# schematic.net
KiCad netlist of a schematic drawn in EAGLE
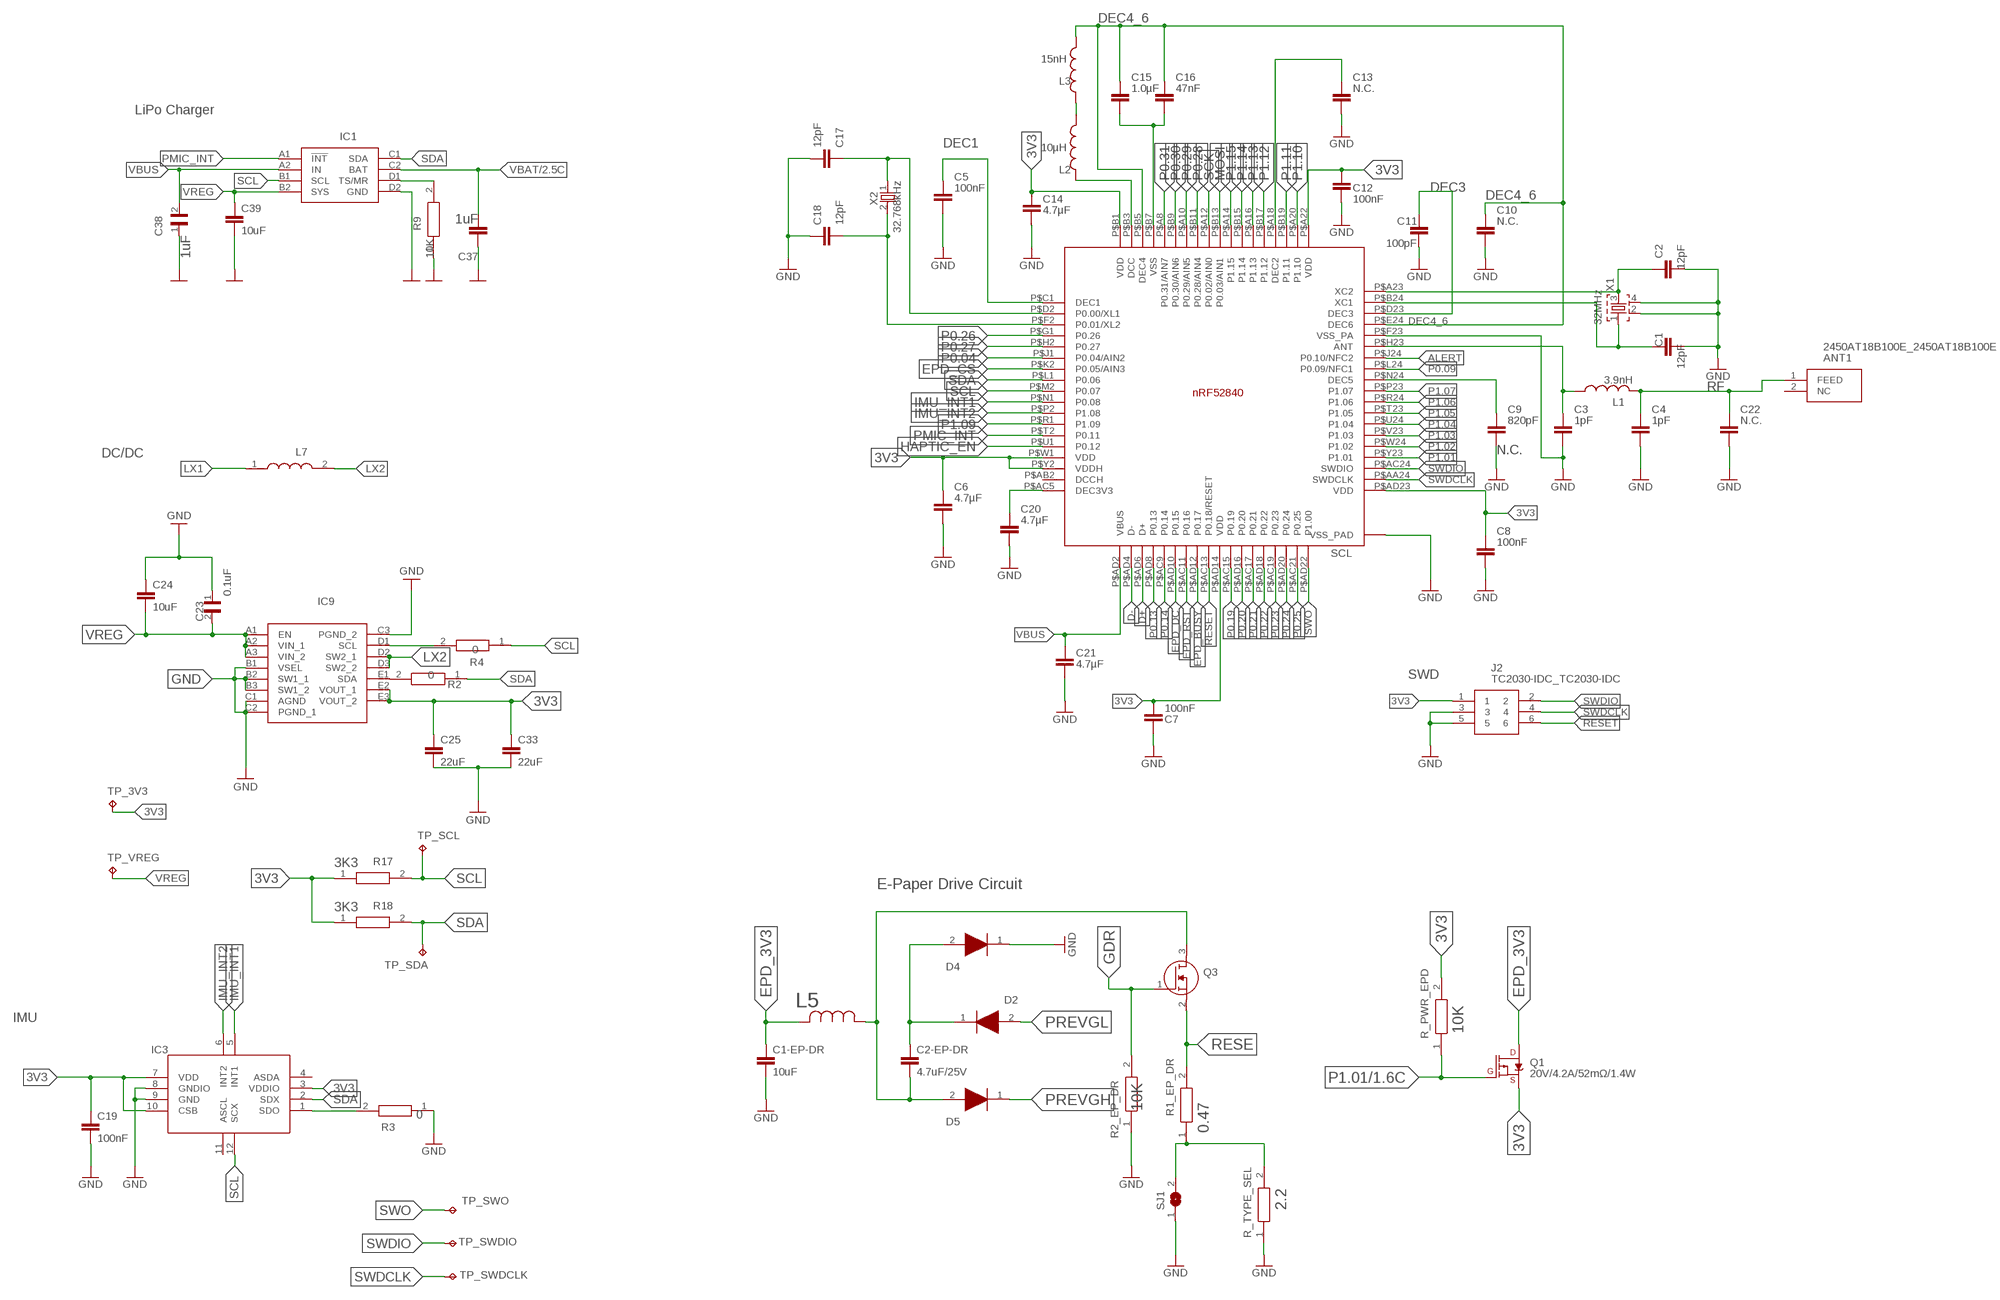
[diagram p0: schematic, sheet 1, part 1 of 2]
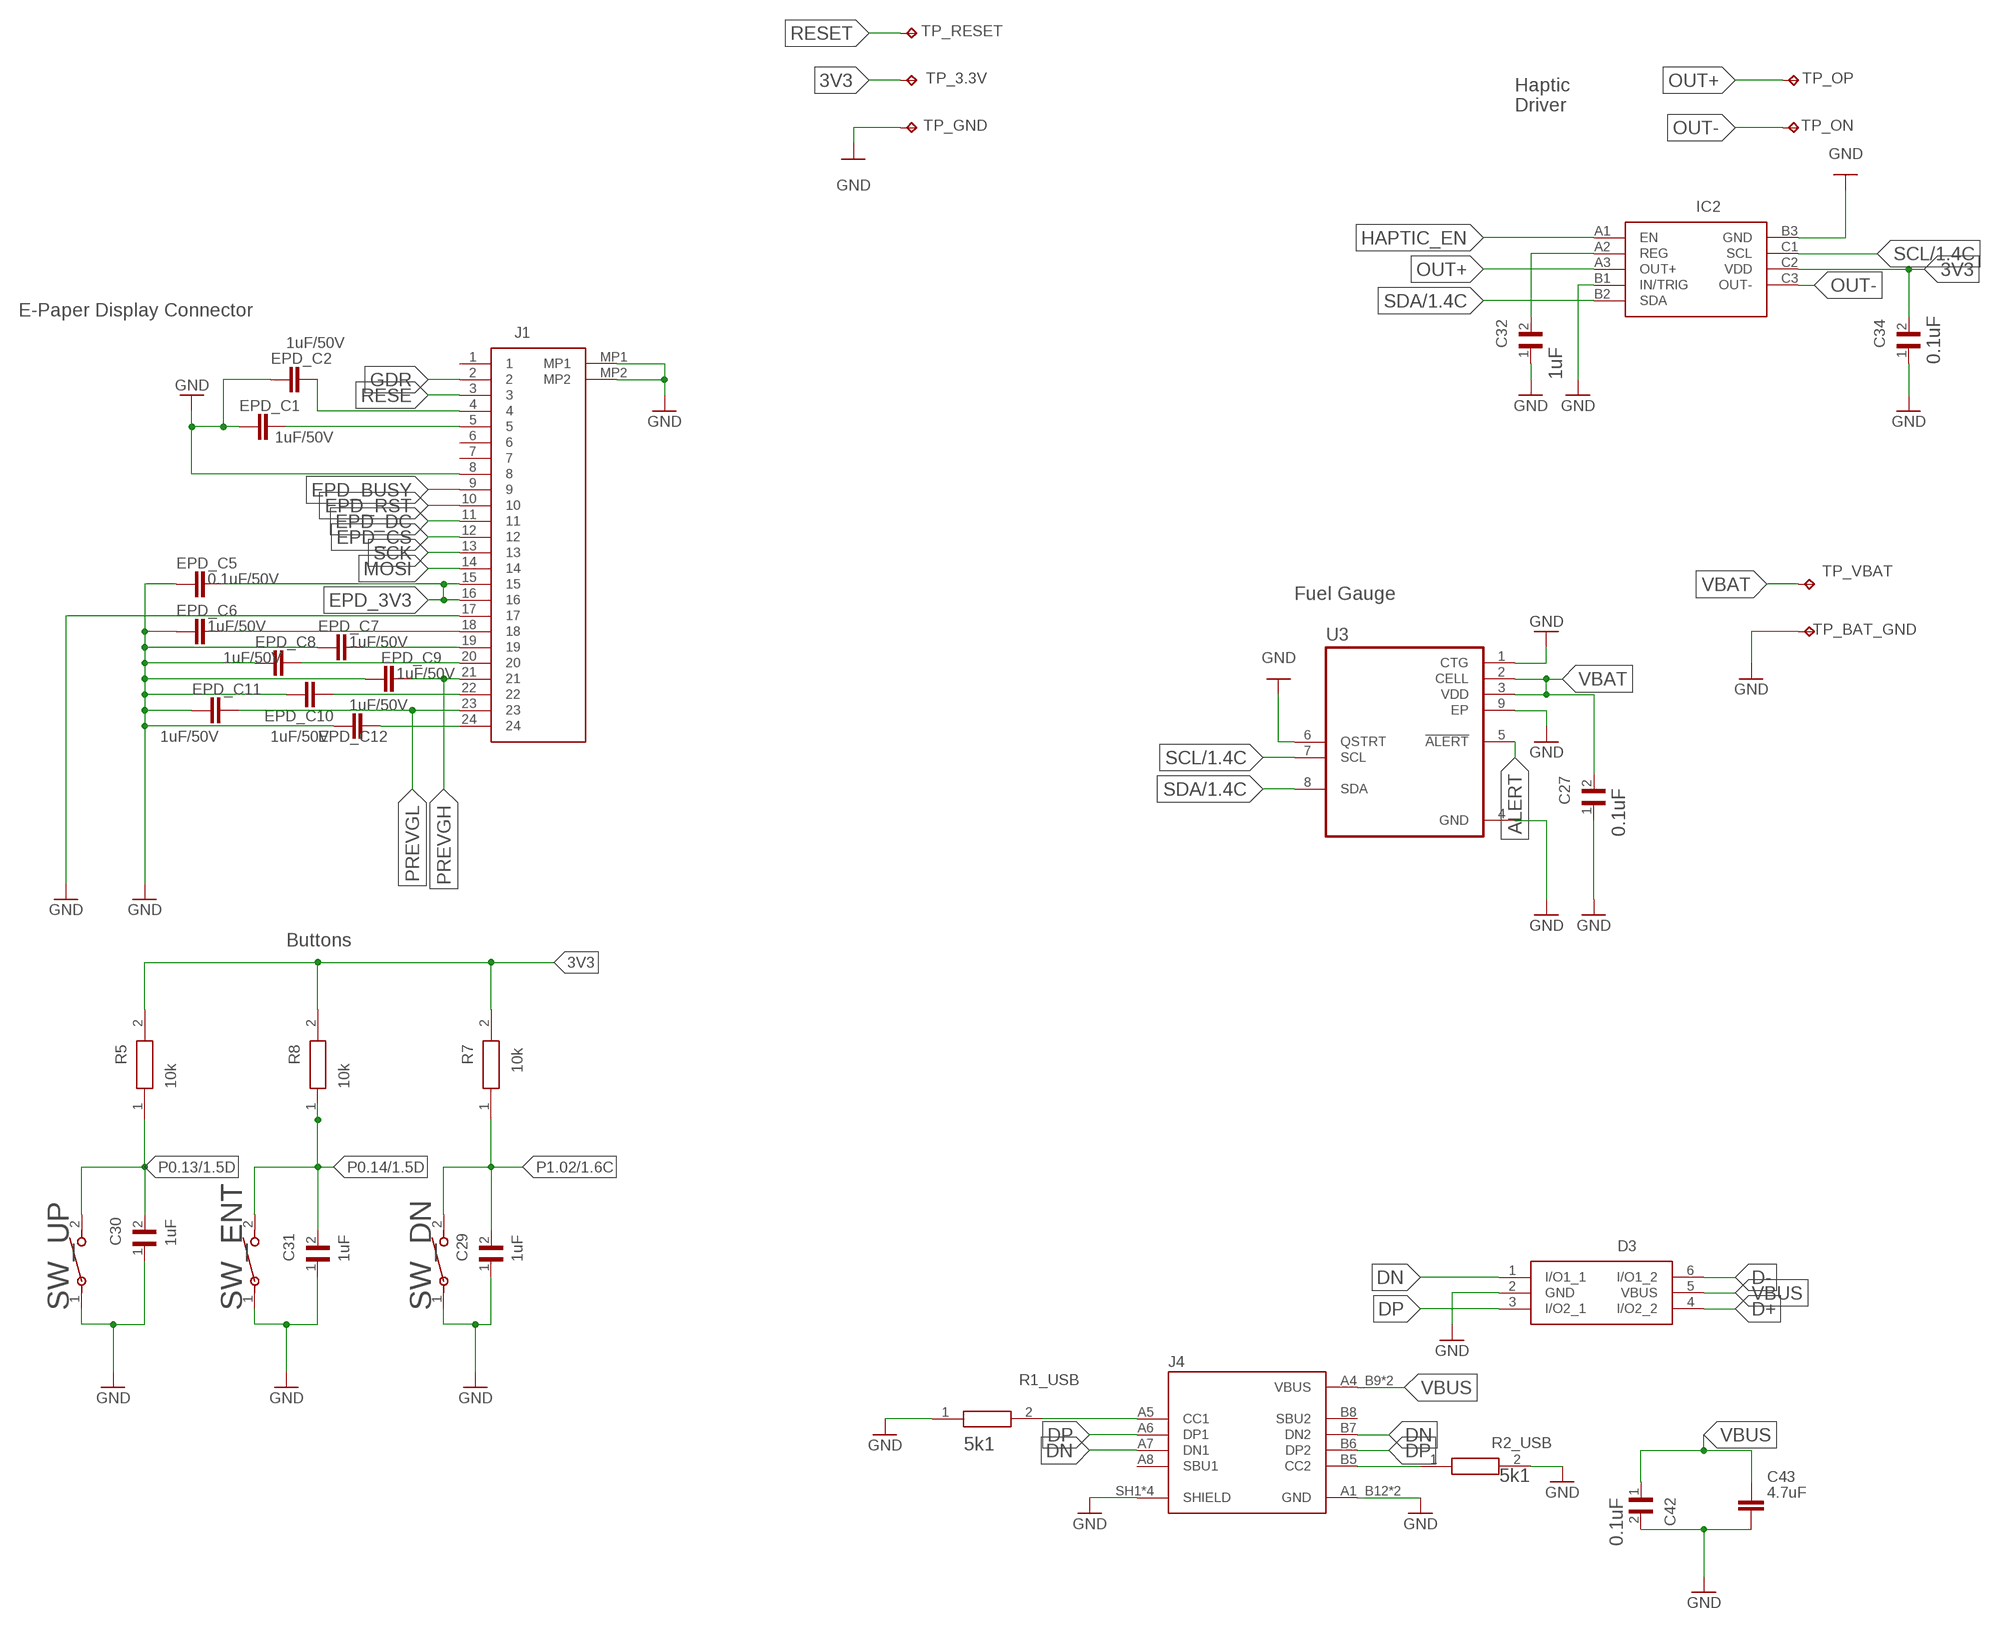
[diagram p1: schematic, sheet 1, part 2 of 2]

(export (version "E")
  (design (tool "Eeschema 10.0.6"))
  (components
    (comp (ref "ANT1")
      (value "2450AT18B100E_2450AT18B100E")
      (footprint "eagle-import:2450AT18B100E_ANTC3216X140N")
      (fields
        (field (name "ARROW_PART_NUMBER") "2450AT18B100E")
        (field (name "MOUSER_PART_NUMBER") "609-2450AT18B100E")
      )
      (libsource (lib "eagle-import") (part "2450AT18B100E_2450AT18B100E"))
    )
    (comp (ref "C1")
      (value "12pF")
      (footprint "eagle-import:NORDIC_NRF_3_RESC0201_L")
      (libsource (lib "eagle-import") (part "NORDIC_NRF_3_CAPACITOR_0201_L"))
    )
    (comp (ref "C1-EP-DR")
      (value "10uF")
      (footprint "eagle-import:NORDIC_NRF_3_RESC0402_L")
      (libsource (lib "eagle-import") (part "NORDIC_NRF_3_CAPACITOR_0402_L"))
    )
    (comp (ref "C2")
      (value "12pF")
      (footprint "eagle-import:NORDIC_NRF_3_RESC0201_L")
      (libsource (lib "eagle-import") (part "NORDIC_NRF_3_CAPACITOR_0201_L"))
    )
    (comp (ref "C2-EP-DR")
      (value "4.7uF/25V")
      (footprint "eagle-import:NORDIC_NRF_3_RESC0402_L")
      (libsource (lib "eagle-import") (part "NORDIC_NRF_3_CAPACITOR_0402_L"))
    )
    (comp (ref "C3")
      (value "1pF")
      (footprint "eagle-import:NORDIC_NRF_3_RESC0201_L")
      (libsource (lib "eagle-import") (part "NORDIC_NRF_3_CAPACITOR_0201_L"))
    )
    (comp (ref "C4")
      (value "1pF")
      (footprint "eagle-import:NORDIC_NRF_3_RESC0201_L")
      (libsource (lib "eagle-import") (part "NORDIC_NRF_3_CAPACITOR_0201_L"))
    )
    (comp (ref "C5")
      (value "100nF")
      (footprint "eagle-import:NORDIC_NRF_3_RESC0201_L")
      (libsource (lib "eagle-import") (part "NORDIC_NRF_3_CAPACITOR_0201_L"))
    )
    (comp (ref "C6")
      (value "4.7µF")
      (footprint "eagle-import:NORDIC_NRF_3_RESC0402_L")
      (libsource (lib "eagle-import") (part "NORDIC_NRF_3_CAPACITOR_0402_L"))
    )
    (comp (ref "C7")
      (value "100nF")
      (footprint "eagle-import:NORDIC_NRF_3_RESC0201_L")
      (libsource (lib "eagle-import") (part "NORDIC_NRF_3_CAPACITOR_0201_L"))
    )
    (comp (ref "C8")
      (value "100nF")
      (footprint "eagle-import:NORDIC_NRF_3_RESC0201_L")
      (libsource (lib "eagle-import") (part "NORDIC_NRF_3_CAPACITOR_0201_L"))
    )
    (comp (ref "C9")
      (value "820pF")
      (footprint "eagle-import:NORDIC_NRF_3_RESC0201_L")
      (libsource (lib "eagle-import") (part "NORDIC_NRF_3_CAPACITOR_0201_L"))
    )
    (comp (ref "C10")
      (value "N.C.")
      (footprint "eagle-import:NORDIC_NRF_3_RESC0201_L")
      (libsource (lib "eagle-import") (part "NORDIC_NRF_3_CAPACITOR_0201_L"))
    )
    (comp (ref "C11")
      (value "100pF")
      (footprint "eagle-import:NORDIC_NRF_3_RESC0201_L")
      (libsource (lib "eagle-import") (part "NORDIC_NRF_3_CAPACITOR_0201_L"))
    )
    (comp (ref "C12")
      (value "100nF")
      (footprint "eagle-import:NORDIC_NRF_3_RESC0201_L")
      (libsource (lib "eagle-import") (part "NORDIC_NRF_3_CAPACITOR_0201_L"))
    )
    (comp (ref "C13")
      (value "N.C.")
      (footprint "eagle-import:NORDIC_NRF_3_RESC0201_L")
      (libsource (lib "eagle-import") (part "NORDIC_NRF_3_CAPACITOR_0201_L"))
    )
    (comp (ref "C14")
      (value "4.7µF")
      (footprint "eagle-import:NORDIC_NRF_3_RESC0402_L")
      (libsource (lib "eagle-import") (part "NORDIC_NRF_3_CAPACITOR_0402_L"))
    )
    (comp (ref "C15")
      (value "1.0µF")
      (footprint "eagle-import:NORDIC_NRF_3_RESC0402_L")
      (libsource (lib "eagle-import") (part "NORDIC_NRF_3_CAPACITOR_0402_L"))
    )
    (comp (ref "C16")
      (value "47nF")
      (footprint "eagle-import:NORDIC_NRF_3_RESC0201_L")
      (libsource (lib "eagle-import") (part "NORDIC_NRF_3_CAPACITOR_0201_L"))
    )
    (comp (ref "C17")
      (value "12pF")
      (footprint "eagle-import:NORDIC_NRF_3_RESC0201_L")
      (libsource (lib "eagle-import") (part "NORDIC_NRF_3_CAPACITOR_0201_L"))
    )
    (comp (ref "C18")
      (value "12pF")
      (footprint "eagle-import:NORDIC_NRF_3_RESC0201_L")
      (libsource (lib "eagle-import") (part "NORDIC_NRF_3_CAPACITOR_0201_L"))
    )
    (comp (ref "C19")
      (value "100nF")
      (footprint "eagle-import:NORDIC_NRF_3_RESC0201_L")
      (libsource (lib "eagle-import") (part "NORDIC_NRF_3_CAPACITOR_0201_L"))
    )
    (comp (ref "C20")
      (value "4.7µF")
      (footprint "eagle-import:NORDIC_NRF_3_RESC0402_L")
      (libsource (lib "eagle-import") (part "NORDIC_NRF_3_CAPACITOR_0402_L"))
    )
    (comp (ref "C21")
      (value "4.7µF")
      (footprint "eagle-import:NORDIC_NRF_3_RESC0402_L")
      (libsource (lib "eagle-import") (part "NORDIC_NRF_3_CAPACITOR_0402_L"))
    )
    (comp (ref "C22")
      (value "N.C.")
      (footprint "eagle-import:NORDIC_NRF_3_RESC0201_L")
      (libsource (lib "eagle-import") (part "NORDIC_NRF_3_CAPACITOR_0201_L"))
    )
    (comp (ref "C23")
      (value "GRM011R60J152KE01L_2_GRM011R60J152KE01L")
      (footprint "eagle-import:GRM011R60J152KE01L_2_CAPC0201X13N")
      (fields
        (field (name "MF") "Murata")
        (field (name "MP") "GRM011R60J152KE01L")
        (field (name "C23") "0.1uF")
      )
      (libsource (lib "eagle-import") (part "GRM011R60J152KE01L_2_GRM011R60J152KE01L"))
    )
    (comp (ref "C24")
      (value "10uF")
      (footprint "eagle-import:NORDIC_NRF_3_RESC0402_L")
      (libsource (lib "eagle-import") (part "NORDIC_NRF_3_CAPACITOR_0402_L"))
    )
    (comp (ref "C25")
      (value "22uF")
      (footprint "eagle-import:NORDIC_NRF_3_RESC0402_L")
      (libsource (lib "eagle-import") (part "NORDIC_NRF_3_CAPACITOR_0402_L"))
    )
    (comp (ref "C27")
      (value "GRM011R60J152KE01L_2_GRM011R60J152KE01L")
      (footprint "eagle-import:GRM011R60J152KE01L_2_CAPC0201X13N")
      (fields
        (field (name "MF") "Murata")
        (field (name "MP") "GRM011R60J152KE01L")
        (field (name "C27") "0.1uF")
      )
      (libsource (lib "eagle-import") (part "GRM011R60J152KE01L_2_GRM011R60J152KE01L"))
    )
    (comp (ref "C29")
      (value "GRM011R60J152KE01L_2_GRM011R60J152KE01L")
      (footprint "eagle-import:GRM011R60J152KE01L_2_CAPC0201X13N")
      (fields
        (field (name "MF") "Murata")
        (field (name "MP") "GRM011R60J152KE01L")
        (field (name "C29") "1uF")
      )
      (libsource (lib "eagle-import") (part "GRM011R60J152KE01L_2_GRM011R60J152KE01L"))
    )
    (comp (ref "C30")
      (value "GRM011R60J152KE01L_2_GRM011R60J152KE01L")
      (footprint "eagle-import:GRM011R60J152KE01L_2_CAPC0201X13N")
      (fields
        (field (name "MF") "Murata")
        (field (name "MP") "GRM011R60J152KE01L")
        (field (name "C30") "1uF")
      )
      (libsource (lib "eagle-import") (part "GRM011R60J152KE01L_2_GRM011R60J152KE01L"))
    )
    (comp (ref "C31")
      (value "GRM011R60J152KE01L_2_GRM011R60J152KE01L")
      (footprint "eagle-import:GRM011R60J152KE01L_2_CAPC0201X13N")
      (fields
        (field (name "MF") "Murata")
        (field (name "MP") "GRM011R60J152KE01L")
        (field (name "C31") "1uF")
      )
      (libsource (lib "eagle-import") (part "GRM011R60J152KE01L_2_GRM011R60J152KE01L"))
    )
    (comp (ref "C32")
      (value "GRM011R60J152KE01L_2_GRM011R60J152KE01L")
      (footprint "eagle-import:GRM011R60J152KE01L_2_CAPC0201X13N")
      (fields
        (field (name "MF") "Murata")
        (field (name "MP") "GRM011R60J152KE01L")
        (field (name "C32") "1uF")
      )
      (libsource (lib "eagle-import") (part "GRM011R60J152KE01L_2_GRM011R60J152KE01L"))
    )
    (comp (ref "C33")
      (value "22uF")
      (footprint "eagle-import:NORDIC_NRF_3_RESC0402_L")
      (libsource (lib "eagle-import") (part "NORDIC_NRF_3_CAPACITOR_0402_L"))
    )
    (comp (ref "C34")
      (value "GRM011R60J152KE01L_2_GRM011R60J152KE01L")
      (footprint "eagle-import:GRM011R60J152KE01L_2_CAPC0201X13N")
      (fields
        (field (name "MF") "Murata")
        (field (name "MP") "GRM011R60J152KE01L")
        (field (name "C34") "0.1uF")
      )
      (libsource (lib "eagle-import") (part "GRM011R60J152KE01L_2_GRM011R60J152KE01L"))
    )
    (comp (ref "C37")
      (value "NORDIC_NRF_3_CAPACITOR_0402_L")
      (footprint "eagle-import:NORDIC_NRF_3_RESC0402_L")
      (fields (field (name "GF") "1uF"))
      (libsource (lib "eagle-import") (part "NORDIC_NRF_3_CAPACITOR_0402_L"))
    )
    (comp (ref "C38")
      (value "GRM011R60J152KE01L_2_GRM011R60J152KE01L")
      (footprint "eagle-import:GRM011R60J152KE01L_2_CAPC0201X13N")
      (fields (field (name "MF") "Murata") (field (name "MP") "GRM011R60J152KE01L") (field (name "D") "1uF"))
      (libsource (lib "eagle-import") (part "GRM011R60J152KE01L_2_GRM011R60J152KE01L"))
    )
    (comp (ref "C39")
      (value "10uF")
      (footprint "eagle-import:NORDIC_NRF_3_RESC0402_L")
      (libsource (lib "eagle-import") (part "NORDIC_NRF_3_CAPACITOR_0402_L"))
    )
    (comp (ref "C42")
      (value "GRM011R60J152KE01L_2_GRM011R60J152KE01L")
      (footprint "eagle-import:GRM011R60J152KE01L_2_CAPC0201X13N")
      (fields
        (field (name "MF") "Murata")
        (field (name "MP") "GRM011R60J152KE01L")
        (field (name "C42") "0.1uF")
      )
      (libsource (lib "eagle-import") (part "GRM011R60J152KE01L_2_GRM011R60J152KE01L"))
    )
    (comp (ref "C43")
      (value "4.7uF")
      (footprint "eagle-import:NORDIC_NRF_3_RESC0402_L")
      (libsource (lib "eagle-import") (part "NORDIC_NRF_3_CAPACITOR_0402_L"))
    )
    (comp (ref "D2")
      (value "ESP32_C6_LIBRARY_5_MBR0530")
      (footprint "eagle-import:ESP32_C6_LIBRARY_5_SOD3716X135N")
      (fields (field (name "MF") "ON Semiconductor") (field (name "MP") "MBR0530"))
      (libsource (lib "eagle-import") (part "ESP32_C6_LIBRARY_5_MBR0530"))
    )
    (comp (ref "D3")
      (value "ESP32_C6_LIBRARY_3_USBLC6-2SC6Y")
      (footprint "eagle-import:ESP32_C6_LIBRARY_3_SOT95P280X145-6N")
      (fields (field (name "MF") "STMicroelectronics") (field (name "MP") "USBLC6-2SC6Y"))
      (libsource (lib "eagle-import") (part "ESP32_C6_LIBRARY_3_USBLC6-2SC6Y"))
    )
    (comp (ref "D4")
      (value "ESP32_C6_LIBRARY_5_MBR0530")
      (footprint "eagle-import:ESP32_C6_LIBRARY_5_SOD3716X135N")
      (fields (field (name "MF") "ON Semiconductor") (field (name "MP") "MBR0530"))
      (libsource (lib "eagle-import") (part "ESP32_C6_LIBRARY_5_MBR0530"))
    )
    (comp (ref "D5")
      (value "ESP32_C6_LIBRARY_5_MBR0530")
      (footprint "eagle-import:ESP32_C6_LIBRARY_5_SOD3716X135N")
      (fields (field (name "MF") "ON Semiconductor") (field (name "MP") "MBR0530"))
      (libsource (lib "eagle-import") (part "ESP32_C6_LIBRARY_5_MBR0530"))
    )
    (comp (ref "EPD_C1")
      (value "1uF/50V")
      (footprint "eagle-import:NORDIC_NRF_3_RESC0402_L")
      (libsource (lib "eagle-import") (part "NORDIC_NRF_3_CAPACITOR_0402_L"))
    )
    (comp (ref "EPD_C2")
      (value "1uF/50V")
      (footprint "eagle-import:NORDIC_NRF_3_RESC0402_L")
      (libsource (lib "eagle-import") (part "NORDIC_NRF_3_CAPACITOR_0402_L"))
    )
    (comp (ref "EPD_C5")
      (value "0.1uF/50V")
      (footprint "eagle-import:NORDIC_NRF_3_RESC0402_L")
      (libsource (lib "eagle-import") (part "NORDIC_NRF_3_CAPACITOR_0402_L"))
    )
    (comp (ref "EPD_C6")
      (value "1uF/50V")
      (footprint "eagle-import:NORDIC_NRF_3_RESC0402_L")
      (libsource (lib "eagle-import") (part "NORDIC_NRF_3_CAPACITOR_0402_L"))
    )
    (comp (ref "EPD_C7")
      (value "1uF/50V")
      (footprint "eagle-import:NORDIC_NRF_3_RESC0402_L")
      (libsource (lib "eagle-import") (part "NORDIC_NRF_3_CAPACITOR_0402_L"))
    )
    (comp (ref "EPD_C8")
      (value "1uF/50V")
      (footprint "eagle-import:NORDIC_NRF_3_RESC0402_L")
      (libsource (lib "eagle-import") (part "NORDIC_NRF_3_CAPACITOR_0402_L"))
    )
    (comp (ref "EPD_C9")
      (value "1uF/50V")
      (footprint "eagle-import:NORDIC_NRF_3_RESC0402_L")
      (libsource (lib "eagle-import") (part "NORDIC_NRF_3_CAPACITOR_0402_L"))
    )
    (comp (ref "EPD_C10")
      (value "1uF/50V")
      (footprint "eagle-import:NORDIC_NRF_3_RESC0402_L")
      (libsource (lib "eagle-import") (part "NORDIC_NRF_3_CAPACITOR_0402_L"))
    )
    (comp (ref "EPD_C11")
      (value "1uF/50V")
      (footprint "eagle-import:NORDIC_NRF_3_RESC0402_L")
      (libsource (lib "eagle-import") (part "NORDIC_NRF_3_CAPACITOR_0402_L"))
    )
    (comp (ref "EPD_C12")
      (value "1uF/50V")
      (footprint "eagle-import:NORDIC_NRF_3_RESC0402_L")
      (libsource (lib "eagle-import") (part "NORDIC_NRF_3_CAPACITOR_0402_L"))
    )
    (comp (ref "IC1")
      (value "BQ25180YBGR_BQ25180YBGR")
      (footprint "eagle-import:BQ25180YBGR_BGA8C40P2X4_100X155X50")
      (fields
        (field (name "ARROW_PART_NUMBER") "BQ25180YBGR")
        (field (name "MOUSER_PART_NUMBER") "595-BQ25180YBGR")
      )
      (libsource (lib "eagle-import") (part "BQ25180YBGR_BQ25180YBGR"))
    )
    (comp (ref "IC2")
      (value "DRV2605YZFR_DRV2605YZFR")
      (footprint "eagle-import:DRV2605YZFR_BGA9C50P3X3_144X144X62")
      (fields (field (name "ARROW_PART_NUMBER") "DRV2605YZFR"))
      (libsource (lib "eagle-import") (part "DRV2605YZFR_DRV2605YZFR"))
    )
    (comp (ref "IC3")
      (value "BMA423_BMA423")
      (footprint "eagle-import:BMA423_BMA423")
      (fields (field (name "ARROW_PART_NUMBER") "BMA423") (field (name "MOUSER_PART_NUMBER") "262-BMA423"))
      (libsource (lib "eagle-import") (part "BMA423_BMA423"))
    )
    (comp (ref "IC9")
      (value "RT6160AWSC_RT6160AWSC")
      (footprint "eagle-import:RT6160AWSC_BGA15C40P3X5_140X230X60")
      (fields
        (field (name "MANUFACTURER_PART_NUMBER") "RT6160AWSC")
        (field (name "MOUSER_PART_NUMBER") "835-RT6160AWSC")
      )
      (libsource (lib "eagle-import") (part "RT6160AWSC_RT6160AWSC"))
    )
    (comp (ref "J1")
      (value "503480-2400_503480-2400")
      (footprint "eagle-import:503480-2400_5034802400")
      (fields
        (field (name "MANUFACTURER_PART_NUMBER") "503480-2400")
        (field (name "MOUSER_PART_NUMBER") "538-503480-2400")
      )
      (libsource (lib "eagle-import") (part "503480-2400_503480-2400"))
    )
    (comp (ref "J2")
      (value "TC2030-IDC_TC2030-IDC")
      (footprint "eagle-import:TC2030-IDC_TC2030IDC")
      (fields (field (name "MANUFACTURER_PART_NUMBER") "TC2030-IDC"))
      (libsource (lib "eagle-import") (part "TC2030-IDC_TC2030-IDC"))
    )
    (comp (ref "J4")
      (value "KH-TYPE-C-16P_KH-TYPE-C-16P")
      (footprint "eagle-import:KH-TYPE-C-16P_KINGHELM_KH-TYPE-C-16P")
      (fields (field (name "MF") "kinghelm") (field (name "MP") "KH-TYPE-C-16P"))
      (libsource (lib "eagle-import") (part "KH-TYPE-C-16P_KH-TYPE-C-16P"))
    )
    (comp (ref "L1")
      (value "3.9nH")
      (footprint "eagle-import:NORDIC_NRF_2_RESC0201_L")
      (libsource (lib "eagle-import") (part "NORDIC_NRF_2_INDUCTOR_0201_L"))
    )
    (comp (ref "L2")
      (value "10µH")
      (footprint "eagle-import:NORDIC_NRF_2_RESC0201_L")
      (libsource (lib "eagle-import") (part "NORDIC_NRF_2_INDUCTOR_0201_L"))
    )
    (comp (ref "L3")
      (value "15nH")
      (footprint "eagle-import:NORDIC_NRF_2_RESC0201_L")
      (libsource (lib "eagle-import") (part "NORDIC_NRF_2_INDUCTOR_0201_L"))
    )
    (comp (ref "L5")
      (value "10uH")
      (footprint "eagle-import:ESP32_C6_LIBRARY_2_IND_4828-WE-TPC_WRE")
      (fields
        (field (name "MANUFACTURER_PART_NUMBER") "744043680")
        (field (name "COPYRIGHT") "Copyright (C) 2024 Ultra Librarian. All rights reserved.")
      )
      (libsource (lib "eagle-import") (part "ESP32_C6_LIBRARY_2_744043680IND_4828-WE-TPC_WRE"))
    )
    (comp (ref "L7")
      (value "MLP2016SR47MT0S1_FTC252012SR47MBCA")
      (footprint "eagle-import:MLP2016SR47MT0S1_INDC2016X100N")
      (fields (field (name "MANUFACTURER_PART_NUMBER") "FTC252012SR47MBCA"))
      (libsource (lib "eagle-import") (part "MLP2016SR47MT0S1_FTC252012SR47MBCA"))
    )
    (comp (ref "Q1")
      (value "20V/4.2A/52mΩ/1.4W")
      (footprint "eagle-import:ESP32_C6_LIBRARY_4_ESP32_C6_LIBRARY_4_ESP32_C6_LIBRARY_4_ESP32_C6_LIBRARY_4_ESP32_WROVER_SPARKFUN-DISCRETESEMI_SOT23-3")
      (libsource (lib "eagle-import") (part "ESP32_C6_LIBRARY_4_ESP32_WROVER_SPARKFUN-DISCRETESEMI_MOSFET_PCH-DMG2305UX-7"))
    )
    (comp (ref "Q3")
      (value "ESP32_C6_LIBRARY_6_SI1308EDL-T1-GE3")
      (footprint "eagle-import:ESP32_C6_LIBRARY_6_SOT65P210X110-3N")
      (fields (field (name "MF") "Vishay Siliconix") (field (name "MP") "SI1308EDL-T1-GE3"))
      (libsource (lib "eagle-import") (part "ESP32_C6_LIBRARY_6_SI1308EDL-T1-GE3"))
    )
    (comp (ref "R1_EP_DR")
      (value "ERA-1AEB3401C_CPF0201D7K68C1")
      (footprint "eagle-import:ERA-1AEB3401C_0201")
      (fields (field (name "R") "0.47"))
      (libsource (lib "eagle-import") (part "ERA-1AEB3401C_CPF0201D7K68C1"))
    )
    (comp (ref "R1_USB")
      (value "ERA-1AEB3401C_CPF0201D7K68C1")
      (footprint "eagle-import:ERA-1AEB3401C_0201")
      (fields (field (name "R1") "5k1"))
      (libsource (lib "eagle-import") (part "ERA-1AEB3401C_CPF0201D7K68C1"))
    )
    (comp (ref "R2")
      (value "CPF0201D7K68C1_CPF0201D7K68C1")
      (footprint "eagle-import:CPF0201D7K68C1_0201")
      (fields (field (name "R2") "0"))
      (libsource (lib "eagle-import") (part "CPF0201D7K68C1_CPF0201D7K68C1"))
    )
    (comp (ref "R2_EP_DR")
      (value "ERA-1AEB3401C_CPF0201D7K68C1")
      (footprint "eagle-import:ERA-1AEB3401C_0201")
      (fields (field (name "R") "10K"))
      (libsource (lib "eagle-import") (part "ERA-1AEB3401C_CPF0201D7K68C1"))
    )
    (comp (ref "R2_USB")
      (value "ERA-1AEB3401C_CPF0201D7K68C1")
      (footprint "eagle-import:ERA-1AEB3401C_0201")
      (fields (field (name "R2") "5k1"))
      (libsource (lib "eagle-import") (part "ERA-1AEB3401C_CPF0201D7K68C1"))
    )
    (comp (ref "R3")
      (value "ERA-1AEB3401C_CPF0201D7K68C1")
      (footprint "eagle-import:ERA-1AEB3401C_0201")
      (fields (field (name "R3") "0"))
      (libsource (lib "eagle-import") (part "ERA-1AEB3401C_CPF0201D7K68C1"))
    )
    (comp (ref "R4")
      (value "CPF0201D7K68C1_CPF0201D7K68C1")
      (footprint "eagle-import:CPF0201D7K68C1_0201")
      (fields (field (name "R4") "0"))
      (libsource (lib "eagle-import") (part "CPF0201D7K68C1_CPF0201D7K68C1"))
    )
    (comp (ref "R5")
      (value "CPF0201D7K68C1_CPF0201D7K68C1")
      (footprint "eagle-import:CPF0201D7K68C1_0201")
      (fields (field (name "R5") "10k"))
      (libsource (lib "eagle-import") (part "CPF0201D7K68C1_CPF0201D7K68C1"))
    )
    (comp (ref "R7")
      (value "CPF0201D7K68C1_CPF0201D7K68C1")
      (footprint "eagle-import:CPF0201D7K68C1_0201")
      (fields (field (name "R7") "10k"))
      (libsource (lib "eagle-import") (part "CPF0201D7K68C1_CPF0201D7K68C1"))
    )
    (comp (ref "R8")
      (value "CPF0201D7K68C1_CPF0201D7K68C1")
      (footprint "eagle-import:CPF0201D7K68C1_0201")
      (fields (field (name "R7") "10k"))
      (libsource (lib "eagle-import") (part "CPF0201D7K68C1_CPF0201D7K68C1"))
    )
    (comp (ref "R9")
      (value "10k")
      (footprint "eagle-import:CPF0201D7K68C1_0201")
      (fields (field (name "R") "10K"))
      (libsource (lib "eagle-import") (part "CPF0201D7K68C1_CPF0201D7K68C1"))
    )
    (comp (ref "R17")
      (value "CPF0201D7K68C1_CPF0201D7K68C1")
      (footprint "eagle-import:CPF0201D7K68C1_0201")
      (fields (field (name "R17") "3K3"))
      (libsource (lib "eagle-import") (part "CPF0201D7K68C1_CPF0201D7K68C1"))
    )
    (comp (ref "R18")
      (value "CPF0201D7K68C1_CPF0201D7K68C1")
      (footprint "eagle-import:CPF0201D7K68C1_0201")
      (fields (field (name "R18") "3K3"))
      (libsource (lib "eagle-import") (part "CPF0201D7K68C1_CPF0201D7K68C1"))
    )
    (comp (ref "R_PWR_EPD")
      (value "ERA-1AEB3401C_CPF0201D7K68C1")
      (footprint "eagle-import:ERA-1AEB3401C_0201")
      (fields (field (name "R") "10K"))
      (libsource (lib "eagle-import") (part "ERA-1AEB3401C_CPF0201D7K68C1"))
    )
    (comp (ref "R_TYPE_SEL")
      (value "ERA-1AEB3401C_CPF0201D7K68C1")
      (footprint "eagle-import:ERA-1AEB3401C_0201")
      (fields (field (name "R") "2.2"))
      (libsource (lib "eagle-import") (part "ERA-1AEB3401C_CPF0201D7K68C1"))
    )
    (comp (ref "SCL")
      (value "NORDIC_NRF_4_NRF52840_QF")
      (footprint "eagle-import:NORDIC_NRF_4_AQFN50P700X700X85_HS-74N")
      (libsource (lib "eagle-import") (part "NORDIC_NRF_4_NRF52840_QF"))
    )
    (comp (ref "SJ1")
      (value "ESP32_C6_LIBRARY_7_JUMPER_SJ")
      (footprint "eagle-import:ESP32_C6_LIBRARY_7_JUMPER_SJ")
      (libsource (lib "eagle-import") (part "ESP32_C6_LIBRARY_7_JUMPER_SJ"))
    )
    (comp (ref "SW_DN")
      (value "2025-10-22_07-23-44_LIBRARY_EVP-AKE31ASW_EVP-AKE31A_PAN")
      (footprint "eagle-import:2025-10-22_07-23-44_LIBRARY_SW_EVP-AKE31A_PAN")
      (fields
        (field (name "MANUFACTURER_PART_NUMBER") "EVP-AKE31A")
        (field (name "COPYRIGHT") "Copyright (C) 2025 Ultra Librarian. All rights reserved.")
      )
      (libsource (lib "eagle-import") (part "2025-10-22_07-23-44_LIBRARY_EVP-AKE31ASW_EVP-AKE31A_PAN"))
    )
    (comp (ref "SW_ENT")
      (value "2025-10-22_07-23-44_LIBRARY_EVP-AKE31ASW_EVP-AKE31A_PAN")
      (footprint "eagle-import:2025-10-22_07-23-44_LIBRARY_SW_EVP-AKE31A_PAN")
      (fields
        (field (name "MANUFACTURER_PART_NUMBER") "EVP-AKE31A")
        (field (name "COPYRIGHT") "Copyright (C) 2025 Ultra Librarian. All rights reserved.")
      )
      (libsource (lib "eagle-import") (part "2025-10-22_07-23-44_LIBRARY_EVP-AKE31ASW_EVP-AKE31A_PAN"))
    )
    (comp (ref "SW_UP")
      (value "2025-10-22_07-23-44_LIBRARY_EVP-AKE31ASW_EVP-AKE31A_PAN")
      (footprint "eagle-import:2025-10-22_07-23-44_LIBRARY_SW_EVP-AKE31A_PAN")
      (fields
        (field (name "MANUFACTURER_PART_NUMBER") "EVP-AKE31A")
        (field (name "COPYRIGHT") "Copyright (C) 2025 Ultra Librarian. All rights reserved.")
      )
      (libsource (lib "eagle-import") (part "2025-10-22_07-23-44_LIBRARY_EVP-AKE31ASW_EVP-AKE31A_PAN"))
    )
    (comp (ref "TP_3.3V")
      (value "HECTOR_WATCH_1_TPTP20R")
      (footprint "eagle-import:HECTOR_WATCH_1_TP20R")
      (libsource (lib "eagle-import") (part "HECTOR_WATCH_1_TPTP20R"))
    )
    (comp (ref "TP_3V3")
      (value "HECTOR_WATCH_1_TPTP20R")
      (footprint "eagle-import:HECTOR_WATCH_1_TP20R")
      (libsource (lib "eagle-import") (part "HECTOR_WATCH_1_TPTP20R"))
    )
    (comp (ref "TP_BAT_GND")
      (value "HECTOR_WATCH_1_TPTP20R")
      (footprint "eagle-import:HECTOR_WATCH_1_TP20R")
      (libsource (lib "eagle-import") (part "HECTOR_WATCH_1_TPTP20R"))
    )
    (comp (ref "TP_GND")
      (value "HECTOR_WATCH_1_TPTP20R")
      (footprint "eagle-import:HECTOR_WATCH_1_TP20R")
      (libsource (lib "eagle-import") (part "HECTOR_WATCH_1_TPTP20R"))
    )
    (comp (ref "TP_ON")
      (value "HECTOR_WATCH_1_TPTP20R")
      (footprint "eagle-import:HECTOR_WATCH_1_TP20R")
      (libsource (lib "eagle-import") (part "HECTOR_WATCH_1_TPTP20R"))
    )
    (comp (ref "TP_OP")
      (value "HECTOR_WATCH_1_TPTP20R")
      (footprint "eagle-import:HECTOR_WATCH_1_TP20R")
      (libsource (lib "eagle-import") (part "HECTOR_WATCH_1_TPTP20R"))
    )
    (comp (ref "TP_RESET")
      (value "HECTOR_WATCH_1_TPTP20R")
      (footprint "eagle-import:HECTOR_WATCH_1_TP20R")
      (libsource (lib "eagle-import") (part "HECTOR_WATCH_1_TPTP20R"))
    )
    (comp (ref "TP_SCL")
      (value "HECTOR_WATCH_1_TPTP20R")
      (footprint "eagle-import:HECTOR_WATCH_1_TP20R")
      (libsource (lib "eagle-import") (part "HECTOR_WATCH_1_TPTP20R"))
    )
    (comp (ref "TP_SDA")
      (value "HECTOR_WATCH_1_TPTP20R")
      (footprint "eagle-import:HECTOR_WATCH_1_TP20R")
      (libsource (lib "eagle-import") (part "HECTOR_WATCH_1_TPTP20R"))
    )
    (comp (ref "TP_SWDCLK")
      (value "HECTOR_WATCH_1_TPTP20R")
      (footprint "eagle-import:HECTOR_WATCH_1_TP20R")
      (libsource (lib "eagle-import") (part "HECTOR_WATCH_1_TPTP20R"))
    )
    (comp (ref "TP_SWDIO")
      (value "HECTOR_WATCH_1_TPTP20R")
      (footprint "eagle-import:HECTOR_WATCH_1_TP20R")
      (libsource (lib "eagle-import") (part "HECTOR_WATCH_1_TPTP20R"))
    )
    (comp (ref "TP_SWO")
      (value "HECTOR_WATCH_1_TPTP20R")
      (footprint "eagle-import:HECTOR_WATCH_1_TP20R")
      (libsource (lib "eagle-import") (part "HECTOR_WATCH_1_TPTP20R"))
    )
    (comp (ref "TP_VBAT")
      (value "HECTOR_WATCH_1_TPTP20R")
      (footprint "eagle-import:HECTOR_WATCH_1_TP20R")
      (libsource (lib "eagle-import") (part "HECTOR_WATCH_1_TPTP20R"))
    )
    (comp (ref "TP_VREG")
      (value "HECTOR_WATCH_1_TPTP20R")
      (footprint "eagle-import:HECTOR_WATCH_1_TP20R")
      (libsource (lib "eagle-import") (part "HECTOR_WATCH_1_TPTP20R"))
    )
    (comp (ref "U3")
      (value "ESP32_C6_LIBRARY_MAX17048G+T10")
      (footprint "eagle-import:ESP32_C6_LIBRARY_SON50P200X200X80-9N")
      (fields (field (name "MF") "Analog Devices") (field (name "MP") "MAX17048G+T10"))
      (libsource (lib "eagle-import") (part "ESP32_C6_LIBRARY_MAX17048G+T10"))
    )
    (comp (ref "X1")
      (value "32MHz")
      (footprint "eagle-import:NORDIC_NRF_BT-XTAL_2016_N")
      (libsource (lib "eagle-import") (part "NORDIC_NRF_XTAL_32MHZ"))
    )
    (comp (ref "X2")
      (value "32.768kHz")
      (footprint "eagle-import:NORDIC_NRF_1_XTAL_3215_N")
      (libsource (lib "eagle-import") (part "NORDIC_NRF_1_XTAL_32KHZ"))
    )
  )
  (nets
    (net (code "1") (name "3V3") (class "Default")
      (node (ref "C12") (pin "1") (pinfunction "1_1") (pintype "passive"))
      (node (ref "C14") (pin "1") (pinfunction "1_1") (pintype "passive"))
      (node (ref "C19") (pin "1") (pinfunction "1_1") (pintype "passive"))
      (node (ref "C25") (pin "1") (pinfunction "1_1") (pintype "passive"))
      (node (ref "C33") (pin "1") (pinfunction "1_1") (pintype "passive"))
      (node (ref "C34") (pin "2") (pinfunction "2_2") (pintype "passive"))
      (node (ref "C6") (pin "1") (pinfunction "1_1") (pintype "passive"))
      (node (ref "C7") (pin "1") (pinfunction "1_1") (pintype "passive"))
      (node (ref "C8") (pin "1") (pinfunction "1_1") (pintype "passive"))
      (node (ref "IC2") (pin "C2") (pinfunction "VDD_C2") (pintype "bidirectional"))
      (node (ref "IC3") (pin "10") (pinfunction "CSB_10") (pintype "bidirectional"))
      (node (ref "IC3") (pin "3") (pinfunction "VDDIO_3") (pintype "bidirectional"))
      (node (ref "IC3") (pin "7") (pinfunction "VDD_7") (pintype "bidirectional"))
      (node (ref "IC9") (pin "E2") (pinfunction "VOUT_1_E2") (pintype "bidirectional"))
      (node (ref "IC9") (pin "E3") (pinfunction "VOUT_2_E3") (pintype "bidirectional"))
      (node (ref "J2") (pin "1") (pinfunction "1_1") (pintype "bidirectional"))
      (node (ref "Q1") (pin "2") (pinfunction "S_2") (pintype "bidirectional"))
      (node (ref "R17") (pin "1") (pinfunction "1_1") (pintype "bidirectional"))
      (node (ref "R18") (pin "1") (pinfunction "1_1") (pintype "bidirectional"))
      (node (ref "R5") (pin "2") (pinfunction "2_2") (pintype "bidirectional"))
      (node (ref "R7") (pin "2") (pinfunction "2_2") (pintype "bidirectional"))
      (node (ref "R8") (pin "2") (pinfunction "2_2") (pintype "bidirectional"))
      (node (ref "R_PWR_EPD") (pin "2") (pinfunction "2_2") (pintype "bidirectional"))
      (node (ref "SCL") (pin "P$A22") (pinfunction "VDD_P$A22") (pintype "power_in"))
      (node (ref "SCL") (pin "P$AD14") (pinfunction "VDD_P$AD14") (pintype "power_in"))
      (node (ref "SCL") (pin "P$AD23") (pinfunction "VDD_P$AD23") (pintype "power_in"))
      (node (ref "SCL") (pin "P$B1") (pinfunction "VDD_P$B1") (pintype "power_in"))
      (node (ref "SCL") (pin "P$W1") (pinfunction "VDD_P$W1") (pintype "power_in"))
      (node (ref "SCL") (pin "P$Y2") (pinfunction "VDDH_P$Y2") (pintype "power_in"))
      (node (ref "TP_3.3V") (pin "TP") (pinfunction "TP_TP") (pintype "input"))
      (node (ref "TP_3V3") (pin "TP") (pinfunction "TP_TP") (pintype "input"))
    )
    (net (code "2") (name "ALERT") (class "Default")
      (node (ref "SCL") (pin "P$J24") (pinfunction "P0.10/NFC2_P$J24") (pintype "bidirectional"))
      (node (ref "U3") (pin "5") (pinfunction "~{ALERT}_5") (pintype "output"))
    )
    (net (code "3") (name "D+") (class "Default")
      (node (ref "D3") (pin "4") (pinfunction "I/O2_2_4") (pintype "bidirectional"))
      (node (ref "SCL") (pin "P$AD6") (pinfunction "D+_P$AD6") (pintype "bidirectional"))
    )
    (net (code "4") (name "D-") (class "Default")
      (node (ref "D3") (pin "6") (pinfunction "I/O1_2_6") (pintype "bidirectional"))
      (node (ref "SCL") (pin "P$AD4") (pinfunction "D-_P$AD4") (pintype "bidirectional"))
    )
    (net (code "5") (name "DN") (class "Default")
      (node (ref "D3") (pin "1") (pinfunction "I/O1_1_1") (pintype "bidirectional"))
      (node (ref "J4") (pin "A7") (pinfunction "DN1_A7") (pintype "bidirectional"))
      (node (ref "J4") (pin "B7") (pinfunction "DN2_B7") (pintype "bidirectional"))
    )
    (net (code "6") (name "DP") (class "Default")
      (node (ref "D3") (pin "3") (pinfunction "I/O2_1_3") (pintype "bidirectional"))
      (node (ref "J4") (pin "A6") (pinfunction "DP1_A6") (pintype "bidirectional"))
      (node (ref "J4") (pin "B6") (pinfunction "DP2_B6") (pintype "bidirectional"))
    )
    (net (code "7") (name "EPD_3V3") (class "Default")
      (node (ref "C1-EP-DR") (pin "1") (pinfunction "1_1") (pintype "passive"))
      (node (ref "EPD_C5") (pin "2") (pinfunction "2_2") (pintype "passive"))
      (node (ref "J1") (pin "15") (pinfunction "15_15") (pintype "bidirectional"))
      (node (ref "J1") (pin "16") (pinfunction "16_16") (pintype "bidirectional"))
      (node (ref "L5") (pin "2") (pinfunction "2_2") (pintype "passive"))
      (node (ref "Q1") (pin "3") (pinfunction "D_3") (pintype "bidirectional"))
    )
    (net (code "8") (name "EPD_BUSY") (class "Default")
      (node (ref "J1") (pin "9") (pinfunction "9_9") (pintype "bidirectional"))
      (node (ref "SCL") (pin "P$AD12") (pinfunction "P0.17_P$AD12") (pintype "bidirectional"))
    )
    (net (code "9") (name "EPD_CS") (class "Default")
      (node (ref "J1") (pin "12") (pinfunction "12_12") (pintype "bidirectional"))
      (node (ref "SCL") (pin "P$K2") (pinfunction "P0.05/AIN3_P$K2") (pintype "bidirectional"))
    )
    (net (code "10") (name "EPD_DC") (class "Default")
      (node (ref "J1") (pin "11") (pinfunction "11_11") (pintype "bidirectional"))
      (node (ref "SCL") (pin "P$AD10") (pinfunction "P0.15_P$AD10") (pintype "bidirectional"))
    )
    (net (code "11") (name "EPD_RST") (class "Default")
      (node (ref "J1") (pin "10") (pinfunction "10_10") (pintype "bidirectional"))
      (node (ref "SCL") (pin "P$AC11") (pinfunction "P0.16_P$AC11") (pintype "bidirectional"))
    )
    (net (code "12") (name "GDR") (class "Default")
      (node (ref "J1") (pin "2") (pinfunction "2_2") (pintype "bidirectional"))
      (node (ref "Q3") (pin "1") (pinfunction "G_1") (pintype "bidirectional"))
      (node (ref "R2_EP_DR") (pin "2") (pinfunction "2_2") (pintype "bidirectional"))
    )
    (net (code "13") (name "GND") (class "Default")
      (node (ref "C1") (pin "2") (pinfunction "2_2") (pintype "passive"))
      (node (ref "C1-EP-DR") (pin "2") (pinfunction "2_2") (pintype "passive"))
      (node (ref "C10") (pin "2") (pinfunction "2_2") (pintype "passive"))
      (node (ref "C11") (pin "2") (pinfunction "2_2") (pintype "passive"))
      (node (ref "C12") (pin "2") (pinfunction "2_2") (pintype "passive"))
      (node (ref "C13") (pin "2") (pinfunction "2_2") (pintype "passive"))
      (node (ref "C14") (pin "2") (pinfunction "2_2") (pintype "passive"))
      (node (ref "C17") (pin "1") (pinfunction "1_1") (pintype "passive"))
      (node (ref "C18") (pin "1") (pinfunction "1_1") (pintype "passive"))
      (node (ref "C19") (pin "2") (pinfunction "2_2") (pintype "passive"))
      (node (ref "C2") (pin "2") (pinfunction "2_2") (pintype "passive"))
      (node (ref "C20") (pin "2") (pinfunction "2_2") (pintype "passive"))
      (node (ref "C21") (pin "2") (pinfunction "2_2") (pintype "passive"))
      (node (ref "C22") (pin "2") (pinfunction "2_2") (pintype "passive"))
      (node (ref "C23") (pin "1") (pinfunction "1_1") (pintype "passive"))
      (node (ref "C24") (pin "1") (pinfunction "1_1") (pintype "passive"))
      (node (ref "C25") (pin "2") (pinfunction "2_2") (pintype "passive"))
      (node (ref "C27") (pin "1") (pinfunction "1_1") (pintype "passive"))
      (node (ref "C29") (pin "1") (pinfunction "1_1") (pintype "passive"))
      (node (ref "C3") (pin "2") (pinfunction "2_2") (pintype "passive"))
      (node (ref "C30") (pin "1") (pinfunction "1_1") (pintype "passive"))
      (node (ref "C31") (pin "1") (pinfunction "1_1") (pintype "passive"))
      (node (ref "C32") (pin "1") (pinfunction "1_1") (pintype "passive"))
      (node (ref "C33") (pin "2") (pinfunction "2_2") (pintype "passive"))
      (node (ref "C34") (pin "1") (pinfunction "1_1") (pintype "passive"))
      (node (ref "C37") (pin "1") (pinfunction "1_1") (pintype "passive"))
      (node (ref "C38") (pin "1") (pinfunction "1_1") (pintype "passive"))
      (node (ref "C39") (pin "2") (pinfunction "2_2") (pintype "passive"))
      (node (ref "C4") (pin "2") (pinfunction "2_2") (pintype "passive"))
      (node (ref "C42") (pin "2") (pinfunction "2_2") (pintype "passive"))
      (node (ref "C43") (pin "2") (pinfunction "2_2") (pintype "passive"))
      (node (ref "C5") (pin "2") (pinfunction "2_2") (pintype "passive"))
      (node (ref "C6") (pin "2") (pinfunction "2_2") (pintype "passive"))
      (node (ref "C7") (pin "2") (pinfunction "2_2") (pintype "passive"))
      (node (ref "C8") (pin "2") (pinfunction "2_2") (pintype "passive"))
      (node (ref "C9") (pin "2") (pinfunction "2_2") (pintype "passive"))
      (node (ref "D3") (pin "2") (pinfunction "GND_2") (pintype "bidirectional"))
      (node (ref "D4") (pin "1") (pinfunction "K_1") (pintype "bidirectional"))
      (node (ref "EPD_C1") (pin "1") (pinfunction "1_1") (pintype "passive"))
      (node (ref "EPD_C10") (pin "1") (pinfunction "1_1") (pintype "passive"))
      (node (ref "EPD_C11") (pin "1") (pinfunction "1_1") (pintype "passive"))
      (node (ref "EPD_C12") (pin "1") (pinfunction "1_1") (pintype "passive"))
      (node (ref "EPD_C2") (pin "1") (pinfunction "1_1") (pintype "passive"))
      (node (ref "EPD_C5") (pin "1") (pinfunction "1_1") (pintype "passive"))
      (node (ref "EPD_C6") (pin "1") (pinfunction "1_1") (pintype "passive"))
      (node (ref "EPD_C7") (pin "1") (pinfunction "1_1") (pintype "passive"))
      (node (ref "EPD_C8") (pin "1") (pinfunction "1_1") (pintype "passive"))
      (node (ref "EPD_C9") (pin "1") (pinfunction "1_1") (pintype "passive"))
      (node (ref "IC1") (pin "D2") (pinfunction "GND_D2") (pintype "bidirectional"))
      (node (ref "IC2") (pin "B1") (pinfunction "IN/TRIG_B1") (pintype "bidirectional"))
      (node (ref "IC2") (pin "B3") (pinfunction "GND_B3") (pintype "bidirectional"))
      (node (ref "IC3") (pin "8") (pinfunction "GNDIO_8") (pintype "bidirectional"))
      (node (ref "IC3") (pin "9") (pinfunction "GND_9") (pintype "bidirectional"))
      (node (ref "IC9") (pin "B1") (pinfunction "VSEL_B1") (pintype "bidirectional"))
      (node (ref "IC9") (pin "B2") (pinfunction "SW1_1_B2") (pintype "bidirectional"))
      (node (ref "IC9") (pin "B3") (pinfunction "SW1_2_B3") (pintype "bidirectional"))
      (node (ref "IC9") (pin "C1") (pinfunction "AGND_C1") (pintype "bidirectional"))
      (node (ref "IC9") (pin "C2") (pinfunction "PGND_1_C2") (pintype "bidirectional"))
      (node (ref "IC9") (pin "C3") (pinfunction "PGND_2_C3") (pintype "bidirectional"))
      (node (ref "J1") (pin "17") (pinfunction "17_17") (pintype "bidirectional"))
      (node (ref "J1") (pin "8") (pinfunction "8_8") (pintype "bidirectional"))
      (node (ref "J1") (pin "MP1") (pinfunction "MP1_MP1") (pintype "bidirectional"))
      (node (ref "J1") (pin "MP2") (pinfunction "MP2_MP2") (pintype "bidirectional"))
      (node (ref "J2") (pin "3") (pinfunction "3_3") (pintype "bidirectional"))
      (node (ref "J2") (pin "5") (pinfunction "5_5") (pintype "bidirectional"))
      (node (ref "J4") (pin "A12_B1") (pinfunction "GND_A12_B1") (pintype "power_in"))
      (node (ref "J4") (pin "A1_B12") (pinfunction "GND_A1_B12") (pintype "power_in"))
      (node (ref "J4") (pin "SH1") (pinfunction "SHIELD_SH1") (pintype "passive"))
      (node (ref "J4") (pin "SH2") (pinfunction "SHIELD_SH2") (pintype "passive"))
      (node (ref "J4") (pin "SH3") (pinfunction "SHIELD_SH3") (pintype "passive"))
      (node (ref "J4") (pin "SH4") (pinfunction "SHIELD_SH4") (pintype "passive"))
      (node (ref "R1_USB") (pin "1") (pinfunction "1_1") (pintype "bidirectional"))
      (node (ref "R2_EP_DR") (pin "1") (pinfunction "1_1") (pintype "bidirectional"))
      (node (ref "R2_USB") (pin "2") (pinfunction "2_2") (pintype "bidirectional"))
      (node (ref "R3") (pin "1") (pinfunction "1_1") (pintype "bidirectional"))
      (node (ref "R9") (pin "1") (pinfunction "1_1") (pintype "bidirectional"))
      (node (ref "R_TYPE_SEL") (pin "1") (pinfunction "1_1") (pintype "bidirectional"))
      (node (ref "SCL") (pin "P$74") (pinfunction "VSS_PAD_P$74") (pintype "bidirectional"))
      (node (ref "SCL") (pin "P$75") (pinfunction "VSS_PAD_P$75") (pintype "bidirectional"))
      (node (ref "SCL") (pin "P$76") (pinfunction "VSS_PAD_P$76") (pintype "bidirectional"))
      (node (ref "SCL") (pin "P$77") (pinfunction "VSS_PAD_P$77") (pintype "bidirectional"))
      (node (ref "SCL") (pin "P$78") (pinfunction "VSS_PAD_P$78") (pintype "bidirectional"))
      (node (ref "SCL") (pin "P$79") (pinfunction "VSS_PAD_P$79") (pintype "bidirectional"))
      (node (ref "SCL") (pin "P$80") (pinfunction "VSS_PAD_P$80") (pintype "bidirectional"))
      (node (ref "SCL") (pin "P$81") (pinfunction "VSS_PAD_P$81") (pintype "bidirectional"))
      (node (ref "SCL") (pin "P$82") (pinfunction "VSS_PAD_P$82") (pintype "bidirectional"))
      (node (ref "SCL") (pin "P$83") (pinfunction "VSS_PAD_P$83") (pintype "bidirectional"))
      (node (ref "SCL") (pin "P$84") (pinfunction "VSS_PAD_P$84") (pintype "bidirectional"))
      (node (ref "SCL") (pin "P$85") (pinfunction "VSS_PAD_P$85") (pintype "bidirectional"))
      (node (ref "SCL") (pin "P$86") (pinfunction "VSS_PAD_P$86") (pintype "bidirectional"))
      (node (ref "SCL") (pin "P$87") (pinfunction "VSS_PAD_P$87") (pintype "bidirectional"))
      (node (ref "SCL") (pin "P$88") (pinfunction "VSS_PAD_P$88") (pintype "bidirectional"))
      (node (ref "SCL") (pin "P$89") (pinfunction "VSS_PAD_P$89") (pintype "bidirectional"))
      (node (ref "SCL") (pin "P$90") (pinfunction "VSS_PAD_P$90") (pintype "bidirectional"))
      (node (ref "SCL") (pin "P$F23") (pinfunction "VSS_PA_P$F23") (pintype "bidirectional"))
      (node (ref "SJ1") (pin "1") (pinfunction "1_1") (pintype "passive"))
      (node (ref "SW_DN") (pin "1") (pinfunction "1_1") (pintype "passive"))
      (node (ref "SW_ENT") (pin "1") (pinfunction "1_1") (pintype "passive"))
      (node (ref "SW_UP") (pin "1") (pinfunction "1_1") (pintype "passive"))
      (node (ref "TP_BAT_GND") (pin "TP") (pinfunction "TP_TP") (pintype "input"))
      (node (ref "TP_GND") (pin "TP") (pinfunction "TP_TP") (pintype "input"))
      (node (ref "U3") (pin "1") (pinfunction "CTG_1") (pintype "power_in"))
      (node (ref "U3") (pin "4") (pinfunction "GND_4") (pintype "power_in"))
      (node (ref "U3") (pin "6") (pinfunction "QSTRT_6") (pintype "input"))
      (node (ref "U3") (pin "9") (pinfunction "EP_9") (pintype "power_in"))
      (node (ref "X1") (pin "2") (pinfunction "2_2") (pintype "passive"))
      (node (ref "X1") (pin "4") (pinfunction "4_4") (pintype "passive"))
    )
    (net (code "14") (name "HAPTIC_EN") (class "Default")
      (node (ref "IC2") (pin "A1") (pinfunction "EN_A1") (pintype "bidirectional"))
      (node (ref "SCL") (pin "P$U1") (pinfunction "P0.12_P$U1") (pintype "bidirectional"))
    )
    (net (code "15") (name "IMU_INT1") (class "Default")
      (node (ref "IC3") (pin "5") (pinfunction "INT1_5") (pintype "bidirectional"))
      (node (ref "SCL") (pin "P$N1") (pinfunction "P0.08_P$N1") (pintype "bidirectional"))
    )
    (net (code "16") (name "IMU_INT2") (class "Default")
      (node (ref "IC3") (pin "6") (pinfunction "INT2_6") (pintype "bidirectional"))
      (node (ref "SCL") (pin "P$P2") (pinfunction "P1.08_P$P2") (pintype "bidirectional"))
    )
    (net (code "17") (name "LX1") (class "Default")
      (node (ref "L7") (pin "1") (pinfunction "1_1") (pintype "bidirectional"))
    )
    (net (code "18") (name "LX2") (class "Default")
      (node (ref "IC9") (pin "D2") (pinfunction "SW2_1_D2") (pintype "bidirectional"))
      (node (ref "IC9") (pin "D3") (pinfunction "SW2_2_D3") (pintype "bidirectional"))
      (node (ref "L7") (pin "2") (pinfunction "2_2") (pintype "bidirectional"))
    )
    (net (code "19") (name "MOSI") (class "Default")
      (node (ref "J1") (pin "14") (pinfunction "14_14") (pintype "bidirectional"))
      (node (ref "SCL") (pin "P$B13") (pinfunction "P0.03/AIN1_P$B13") (pintype "bidirectional"))
    )
    (net (code "20") (name "Net-(ANT1-FEED)") (class "Default")
      (node (ref "ANT1") (pin "1") (pinfunction "FEED_1") (pintype "input"))
      (node (ref "C22") (pin "1") (pinfunction "1_1") (pintype "passive"))
      (node (ref "C4") (pin "1") (pinfunction "1_1") (pintype "passive"))
      (node (ref "L1") (pin "2") (pinfunction "2_2") (pintype "passive"))
    )
    (net (code "21") (name "Net-(D2-K)") (class "Default")
      (node (ref "C2-EP-DR") (pin "1") (pinfunction "1_1") (pintype "passive"))
      (node (ref "D2") (pin "1") (pinfunction "K_1") (pintype "bidirectional"))
      (node (ref "D4") (pin "2") (pinfunction "A_2") (pintype "bidirectional"))
    )
    (net (code "22") (name "Net-(D5-A)") (class "Default")
      (node (ref "C2-EP-DR") (pin "2") (pinfunction "2_2") (pintype "passive"))
      (node (ref "D5") (pin "2") (pinfunction "A_2") (pintype "bidirectional"))
      (node (ref "L5") (pin "1") (pinfunction "1_1") (pintype "passive"))
      (node (ref "Q3") (pin "3") (pinfunction "D_3") (pintype "bidirectional"))
    )
    (net (code "23") (name "Net-(EPD_C1-Pad2)") (class "Default")
      (node (ref "EPD_C1") (pin "2") (pinfunction "2_2") (pintype "passive"))
      (node (ref "J1") (pin "5") (pinfunction "5_5") (pintype "bidirectional"))
    )
    (net (code "24") (name "Net-(EPD_C2-Pad2)") (class "Default")
      (node (ref "EPD_C2") (pin "2") (pinfunction "2_2") (pintype "passive"))
      (node (ref "J1") (pin "4") (pinfunction "4_4") (pintype "bidirectional"))
    )
    (net (code "25") (name "Net-(EPD_C6-Pad2)") (class "Default")
      (node (ref "EPD_C6") (pin "2") (pinfunction "2_2") (pintype "passive"))
      (node (ref "J1") (pin "18") (pinfunction "18_18") (pintype "bidirectional"))
    )
    (net (code "26") (name "Net-(EPD_C7-Pad2)") (class "Default")
      (node (ref "EPD_C7") (pin "2") (pinfunction "2_2") (pintype "passive"))
      (node (ref "J1") (pin "19") (pinfunction "19_19") (pintype "bidirectional"))
    )
    (net (code "27") (name "Net-(EPD_C8-Pad2)") (class "Default")
      (node (ref "EPD_C8") (pin "2") (pinfunction "2_2") (pintype "passive"))
      (node (ref "J1") (pin "20") (pinfunction "20_20") (pintype "bidirectional"))
    )
    (net (code "28") (name "Net-(EPD_C10-Pad2)") (class "Default")
      (node (ref "EPD_C10") (pin "2") (pinfunction "2_2") (pintype "passive"))
      (node (ref "J1") (pin "22") (pinfunction "22_22") (pintype "bidirectional"))
    )
    (net (code "29") (name "Net-(EPD_C12-Pad2)") (class "Default")
      (node (ref "EPD_C12") (pin "2") (pinfunction "2_2") (pintype "passive"))
      (node (ref "J1") (pin "24") (pinfunction "24_24") (pintype "bidirectional"))
    )
    (net (code "30") (name "Net-(IC1-TS{slash}MR)") (class "Default")
      (node (ref "IC1") (pin "D1") (pinfunction "TS/MR_D1") (pintype "bidirectional"))
      (node (ref "R9") (pin "2") (pinfunction "2_2") (pintype "bidirectional"))
    )
    (net (code "31") (name "Net-(IC2-REG)") (class "Default")
      (node (ref "C32") (pin "2") (pinfunction "2_2") (pintype "passive"))
      (node (ref "IC2") (pin "A2") (pinfunction "REG_A2") (pintype "bidirectional"))
    )
    (net (code "32") (name "Net-(IC3-SDO)") (class "Default")
      (node (ref "IC3") (pin "1") (pinfunction "SDO_1") (pintype "bidirectional"))
      (node (ref "R3") (pin "2") (pinfunction "2_2") (pintype "bidirectional"))
    )
    (net (code "33") (name "Net-(IC9-SCL)") (class "Default")
      (node (ref "IC9") (pin "D1") (pinfunction "SCL_D1") (pintype "bidirectional"))
      (node (ref "R4") (pin "2") (pinfunction "2_2") (pintype "bidirectional"))
    )
    (net (code "34") (name "Net-(IC9-SDA)") (class "Default")
      (node (ref "IC9") (pin "E1") (pinfunction "SDA_E1") (pintype "bidirectional"))
      (node (ref "R2") (pin "2") (pinfunction "2_2") (pintype "bidirectional"))
    )
    (net (code "35") (name "Net-(J4-CC1)") (class "Default")
      (node (ref "J4") (pin "A5") (pinfunction "CC1_A5") (pintype "bidirectional"))
      (node (ref "R1_USB") (pin "2") (pinfunction "2_2") (pintype "bidirectional"))
    )
    (net (code "36") (name "Net-(J4-CC2)") (class "Default")
      (node (ref "J4") (pin "B5") (pinfunction "CC2_B5") (pintype "bidirectional"))
      (node (ref "R2_USB") (pin "1") (pinfunction "1_1") (pintype "bidirectional"))
    )
    (net (code "37") (name "Net-(L2-Pad2)") (class "Default")
      (node (ref "L2") (pin "2") (pinfunction "2_2") (pintype "passive"))
      (node (ref "L3") (pin "1") (pinfunction "1_1") (pintype "passive"))
    )
    (net (code "38") (name "Net-(R1_EP_DR-Pad1)") (class "Default")
      (node (ref "R1_EP_DR") (pin "1") (pinfunction "1_1") (pintype "bidirectional"))
      (node (ref "R_TYPE_SEL") (pin "2") (pinfunction "2_2") (pintype "bidirectional"))
      (node (ref "SJ1") (pin "2") (pinfunction "2_2") (pintype "passive"))
    )
    (net (code "39") (name "Net-(SCL-ANT)") (class "Default")
      (node (ref "C3") (pin "1") (pinfunction "1_1") (pintype "passive"))
      (node (ref "L1") (pin "1") (pinfunction "1_1") (pintype "passive"))
      (node (ref "SCL") (pin "P$H23") (pinfunction "ANT_P$H23") (pintype "bidirectional"))
    )
    (net (code "40") (name "Net-(SCL-DCC)") (class "Default")
      (node (ref "L2") (pin "1") (pinfunction "1_1") (pintype "passive"))
      (node (ref "SCL") (pin "P$B3") (pinfunction "DCC_P$B3") (pintype "output"))
    )
    (net (code "41") (name "Net-(SCL-DEC1)") (class "Default")
      (node (ref "C5") (pin "1") (pinfunction "1_1") (pintype "passive"))
      (node (ref "SCL") (pin "P$C1") (pinfunction "DEC1_P$C1") (pintype "power_in"))
    )
    (net (code "42") (name "Net-(SCL-DEC2)") (class "Default")
      (node (ref "C13") (pin "1") (pinfunction "1_1") (pintype "passive"))
      (node (ref "SCL") (pin "P$A18") (pinfunction "DEC2_P$A18") (pintype "bidirectional"))
    )
    (net (code "43") (name "Net-(SCL-DEC3)") (class "Default")
      (node (ref "C11") (pin "1") (pinfunction "1_1") (pintype "passive"))
      (node (ref "SCL") (pin "P$D23") (pinfunction "DEC3_P$D23") (pintype "bidirectional"))
    )
    (net (code "44") (name "Net-(SCL-DEC3V3)") (class "Default")
      (node (ref "C20") (pin "1") (pinfunction "1_1") (pintype "passive"))
      (node (ref "SCL") (pin "P$AC5") (pinfunction "DEC3V3_P$AC5") (pintype "bidirectional"))
    )
    (net (code "45") (name "Net-(SCL-DEC4)") (class "Default")
      (node (ref "C10") (pin "1") (pinfunction "1_1") (pintype "passive"))
      (node (ref "C15") (pin "1") (pinfunction "1_1") (pintype "passive"))
      (node (ref "C16") (pin "1") (pinfunction "1_1") (pintype "passive"))
      (node (ref "L3") (pin "2") (pinfunction "2_2") (pintype "passive"))
      (node (ref "SCL") (pin "P$B5") (pinfunction "DEC4_P$B5") (pintype "power_in"))
      (node (ref "SCL") (pin "P$E24") (pinfunction "DEC6_P$E24") (pintype "bidirectional"))
    )
    (net (code "46") (name "Net-(SCL-DEC5)") (class "Default")
      (node (ref "C9") (pin "1") (pinfunction "1_1") (pintype "passive"))
      (node (ref "SCL") (pin "P$N24") (pinfunction "DEC5_P$N24") (pintype "bidirectional"))
    )
    (net (code "47") (name "Net-(SCL-P0.00{slash}XL1)") (class "Default")
      (node (ref "C17") (pin "2") (pinfunction "2_2") (pintype "passive"))
      (node (ref "SCL") (pin "P$D2") (pinfunction "P0.00/XL1_P$D2") (pintype "bidirectional"))
      (node (ref "X2") (pin "1") (pinfunction "1_1") (pintype "passive"))
    )
    (net (code "48") (name "Net-(SCL-P0.01{slash}XL2)") (class "Default")
      (node (ref "C18") (pin "2") (pinfunction "2_2") (pintype "passive"))
      (node (ref "SCL") (pin "P$F2") (pinfunction "P0.01/XL2_P$F2") (pintype "bidirectional"))
      (node (ref "X2") (pin "2") (pinfunction "2_2") (pintype "passive"))
    )
    (net (code "49") (name "Net-(SCL-VSS)") (class "Default")
      (node (ref "C15") (pin "2") (pinfunction "2_2") (pintype "passive"))
      (node (ref "C16") (pin "2") (pinfunction "2_2") (pintype "passive"))
      (node (ref "SCL") (pin "P$B7") (pinfunction "VSS_P$B7") (pintype "power_in"))
    )
    (net (code "50") (name "Net-(SCL-XC1)") (class "Default")
      (node (ref "C1") (pin "1") (pinfunction "1_1") (pintype "passive"))
      (node (ref "SCL") (pin "P$B24") (pinfunction "XC1_P$B24") (pintype "input"))
      (node (ref "X1") (pin "1") (pinfunction "1_1") (pintype "passive"))
    )
    (net (code "51") (name "Net-(SCL-XC2)") (class "Default")
      (node (ref "C2") (pin "1") (pinfunction "1_1") (pintype "passive"))
      (node (ref "SCL") (pin "P$A23") (pinfunction "XC2_P$A23") (pintype "output"))
      (node (ref "X1") (pin "3") (pinfunction "3_3") (pintype "passive"))
    )
    (net (code "52") (name "OUT+") (class "Default")
      (node (ref "IC2") (pin "A3") (pinfunction "OUT+_A3") (pintype "bidirectional"))
      (node (ref "TP_OP") (pin "TP") (pinfunction "TP_TP") (pintype "input"))
    )
    (net (code "53") (name "OUT-") (class "Default")
      (node (ref "IC2") (pin "C3") (pinfunction "OUT-_C3") (pintype "bidirectional"))
      (node (ref "TP_ON") (pin "TP") (pinfunction "TP_TP") (pintype "input"))
    )
    (net (code "54") (name "P0.04") (class "Default")
      (node (ref "SCL") (pin "P$J1") (pinfunction "P0.04/AIN2_P$J1") (pintype "bidirectional"))
    )
    (net (code "55") (name "P0.09") (class "Default")
      (node (ref "SCL") (pin "P$L24") (pinfunction "P0.09/NFC1_P$L24") (pintype "bidirectional"))
    )
    (net (code "56") (name "P0.13") (class "Default")
      (node (ref "SCL") (pin "P$AD8") (pinfunction "P0.13_P$AD8") (pintype "bidirectional"))
    )
    (net (code "57") (name "P0.13{slash}1.5D") (class "Default")
      (node (ref "C30") (pin "2") (pinfunction "2_2") (pintype "passive"))
      (node (ref "R5") (pin "1") (pinfunction "1_1") (pintype "bidirectional"))
      (node (ref "SW_UP") (pin "2") (pinfunction "2_2") (pintype "passive"))
    )
    (net (code "58") (name "P0.14") (class "Default")
      (node (ref "SCL") (pin "P$AC9") (pinfunction "P0.14_P$AC9") (pintype "bidirectional"))
    )
    (net (code "59") (name "P0.14{slash}1.5D") (class "Default")
      (node (ref "C31") (pin "2") (pinfunction "2_2") (pintype "passive"))
      (node (ref "R8") (pin "1") (pinfunction "1_1") (pintype "bidirectional"))
      (node (ref "SW_ENT") (pin "2") (pinfunction "2_2") (pintype "passive"))
    )
    (net (code "60") (name "P0.19") (class "Default")
      (node (ref "SCL") (pin "P$AC15") (pinfunction "P0.19_P$AC15") (pintype "bidirectional"))
    )
    (net (code "61") (name "P0.20") (class "Default")
      (node (ref "SCL") (pin "P$AD16") (pinfunction "P0.20_P$AD16") (pintype "bidirectional"))
    )
    (net (code "62") (name "P0.21") (class "Default")
      (node (ref "SCL") (pin "P$AC17") (pinfunction "P0.21_P$AC17") (pintype "bidirectional"))
    )
    (net (code "63") (name "P0.22") (class "Default")
      (node (ref "SCL") (pin "P$AD18") (pinfunction "P0.22_P$AD18") (pintype "bidirectional"))
    )
    (net (code "64") (name "P0.23") (class "Default")
      (node (ref "SCL") (pin "P$AC19") (pinfunction "P0.23_P$AC19") (pintype "bidirectional"))
    )
    (net (code "65") (name "P0.24") (class "Default")
      (node (ref "SCL") (pin "P$AD20") (pinfunction "P0.24_P$AD20") (pintype "bidirectional"))
    )
    (net (code "66") (name "P0.25") (class "Default")
      (node (ref "SCL") (pin "P$AC21") (pinfunction "P0.25_P$AC21") (pintype "bidirectional"))
    )
    (net (code "67") (name "P0.26") (class "Default")
      (node (ref "SCL") (pin "P$G1") (pinfunction "P0.26_P$G1") (pintype "bidirectional"))
    )
    (net (code "68") (name "P0.27") (class "Default")
      (node (ref "SCL") (pin "P$H2") (pinfunction "P0.27_P$H2") (pintype "bidirectional"))
    )
    (net (code "69") (name "P0.28") (class "Default")
      (node (ref "SCL") (pin "P$B11") (pinfunction "P0.28/AIN4_P$B11") (pintype "bidirectional"))
    )
    (net (code "70") (name "P0.29") (class "Default")
      (node (ref "SCL") (pin "P$A10") (pinfunction "P0.29/AIN5_P$A10") (pintype "bidirectional"))
    )
    (net (code "71") (name "P0.30") (class "Default")
      (node (ref "SCL") (pin "P$B9") (pinfunction "P0.30/AIN6_P$B9") (pintype "bidirectional"))
    )
    (net (code "72") (name "P0.31") (class "Default")
      (node (ref "SCL") (pin "P$A8") (pinfunction "P0.31/AIN7_P$A8") (pintype "bidirectional"))
    )
    (net (code "73") (name "P1.01") (class "Default")
      (node (ref "SCL") (pin "P$Y23") (pinfunction "P1.01_P$Y23") (pintype "bidirectional"))
    )
    (net (code "74") (name "P1.01{slash}1.6C") (class "Default")
      (node (ref "Q1") (pin "1") (pinfunction "G_1") (pintype "bidirectional"))
      (node (ref "R_PWR_EPD") (pin "1") (pinfunction "1_1") (pintype "bidirectional"))
    )
    (net (code "75") (name "P1.02") (class "Default")
      (node (ref "SCL") (pin "P$W24") (pinfunction "P1.02_P$W24") (pintype "bidirectional"))
    )
    (net (code "76") (name "P1.02{slash}1.6C") (class "Default")
      (node (ref "C29") (pin "2") (pinfunction "2_2") (pintype "passive"))
      (node (ref "R7") (pin "1") (pinfunction "1_1") (pintype "bidirectional"))
      (node (ref "SW_DN") (pin "2") (pinfunction "2_2") (pintype "passive"))
    )
    (net (code "77") (name "P1.03") (class "Default")
      (node (ref "SCL") (pin "P$V23") (pinfunction "P1.03_P$V23") (pintype "bidirectional"))
    )
    (net (code "78") (name "P1.04") (class "Default")
      (node (ref "SCL") (pin "P$U24") (pinfunction "P1.04_P$U24") (pintype "bidirectional"))
    )
    (net (code "79") (name "P1.05") (class "Default")
      (node (ref "SCL") (pin "P$T23") (pinfunction "P1.05_P$T23") (pintype "bidirectional"))
    )
    (net (code "80") (name "P1.06") (class "Default")
      (node (ref "SCL") (pin "P$R24") (pinfunction "P1.06_P$R24") (pintype "bidirectional"))
    )
    (net (code "81") (name "P1.07") (class "Default")
      (node (ref "SCL") (pin "P$P23") (pinfunction "P1.07_P$P23") (pintype "bidirectional"))
    )
    (net (code "82") (name "P1.09") (class "Default")
      (node (ref "SCL") (pin "P$R1") (pinfunction "P1.09_P$R1") (pintype "bidirectional"))
    )
    (net (code "83") (name "P1.10") (class "Default")
      (node (ref "SCL") (pin "P$A20") (pinfunction "P1.10_P$A20") (pintype "bidirectional"))
    )
    (net (code "84") (name "P1.11") (class "Default")
      (node (ref "SCL") (pin "P$B19") (pinfunction "P1.11_P$B19") (pintype "bidirectional"))
    )
    (net (code "85") (name "P1.12") (class "Default")
      (node (ref "SCL") (pin "P$B17") (pinfunction "P1.12_P$B17") (pintype "bidirectional"))
    )
    (net (code "86") (name "P1.13") (class "Default")
      (node (ref "SCL") (pin "P$A16") (pinfunction "P1.13_P$A16") (pintype "bidirectional"))
    )
    (net (code "87") (name "P1.14") (class "Default")
      (node (ref "SCL") (pin "P$B15") (pinfunction "P1.14_P$B15") (pintype "bidirectional"))
    )
    (net (code "88") (name "P1.15") (class "Default")
      (node (ref "SCL") (pin "P$A14") (pinfunction "P1.15_P$A14") (pintype "bidirectional"))
    )
    (net (code "89") (name "PMIC_INT") (class "Default")
      (node (ref "IC1") (pin "A1") (pinfunction "~{INT}_A1") (pintype "bidirectional"))
      (node (ref "SCL") (pin "P$T2") (pinfunction "P0.11_P$T2") (pintype "bidirectional"))
    )
    (net (code "90") (name "PREVGH") (class "Default")
      (node (ref "D5") (pin "1") (pinfunction "K_1") (pintype "bidirectional"))
      (node (ref "EPD_C9") (pin "2") (pinfunction "2_2") (pintype "passive"))
      (node (ref "J1") (pin "21") (pinfunction "21_21") (pintype "bidirectional"))
    )
    (net (code "91") (name "PREVGL") (class "Default")
      (node (ref "D2") (pin "2") (pinfunction "A_2") (pintype "bidirectional"))
      (node (ref "EPD_C11") (pin "2") (pinfunction "2_2") (pintype "passive"))
      (node (ref "J1") (pin "23") (pinfunction "23_23") (pintype "bidirectional"))
    )
    (net (code "92") (name "RESE") (class "Default")
      (node (ref "J1") (pin "3") (pinfunction "3_3") (pintype "bidirectional"))
      (node (ref "Q3") (pin "2") (pinfunction "S_2") (pintype "bidirectional"))
      (node (ref "R1_EP_DR") (pin "2") (pinfunction "2_2") (pintype "bidirectional"))
    )
    (net (code "93") (name "RESET") (class "Default")
      (node (ref "J2") (pin "6") (pinfunction "6_6") (pintype "bidirectional"))
      (node (ref "SCL") (pin "P$AC13") (pinfunction "P0.18/RESET_P$AC13") (pintype "bidirectional"))
      (node (ref "TP_RESET") (pin "TP") (pinfunction "TP_TP") (pintype "input"))
    )
    (net (code "94") (name "SCK") (class "Default")
      (node (ref "J1") (pin "13") (pinfunction "13_13") (pintype "bidirectional"))
      (node (ref "SCL") (pin "P$A12") (pinfunction "P0.02/AIN0_P$A12") (pintype "bidirectional"))
    )
    (net (code "95") (name "SCL") (class "Default")
      (node (ref "IC1") (pin "B1") (pinfunction "SCL_B1") (pintype "bidirectional"))
      (node (ref "IC3") (pin "12") (pinfunction "SCX_12") (pintype "bidirectional"))
      (node (ref "R17") (pin "2") (pinfunction "2_2") (pintype "bidirectional"))
      (node (ref "R4") (pin "1") (pinfunction "1_1") (pintype "bidirectional"))
      (node (ref "SCL") (pin "P$M2") (pinfunction "P0.07_P$M2") (pintype "bidirectional"))
      (node (ref "TP_SCL") (pin "TP") (pinfunction "TP_TP") (pintype "input"))
    )
    (net (code "96") (name "SCL{slash}1.4C") (class "Default")
      (node (ref "IC2") (pin "C1") (pinfunction "SCL_C1") (pintype "bidirectional"))
      (node (ref "U3") (pin "7") (pinfunction "SCL_7") (pintype "input"))
    )
    (net (code "97") (name "SDA") (class "Default")
      (node (ref "IC1") (pin "C1") (pinfunction "SDA_C1") (pintype "bidirectional"))
      (node (ref "IC3") (pin "2") (pinfunction "SDX_2") (pintype "bidirectional"))
      (node (ref "R18") (pin "2") (pinfunction "2_2") (pintype "bidirectional"))
      (node (ref "R2") (pin "1") (pinfunction "1_1") (pintype "bidirectional"))
      (node (ref "SCL") (pin "P$L1") (pinfunction "P0.06_P$L1") (pintype "bidirectional"))
      (node (ref "TP_SDA") (pin "TP") (pinfunction "TP_TP") (pintype "input"))
    )
    (net (code "98") (name "SDA{slash}1.4C") (class "Default")
      (node (ref "IC2") (pin "B2") (pinfunction "SDA_B2") (pintype "bidirectional"))
      (node (ref "U3") (pin "8") (pinfunction "SDA_8") (pintype "bidirectional"))
    )
    (net (code "99") (name "SWDCLK") (class "Default")
      (node (ref "J2") (pin "4") (pinfunction "4_4") (pintype "bidirectional"))
      (node (ref "SCL") (pin "P$AA24") (pinfunction "SWDCLK_P$AA24") (pintype "input"))
      (node (ref "TP_SWDCLK") (pin "TP") (pinfunction "TP_TP") (pintype "input"))
    )
    (net (code "100") (name "SWDIO") (class "Default")
      (node (ref "J2") (pin "2") (pinfunction "2_2") (pintype "bidirectional"))
      (node (ref "SCL") (pin "P$AC24") (pinfunction "SWDIO_P$AC24") (pintype "bidirectional"))
      (node (ref "TP_SWDIO") (pin "TP") (pinfunction "TP_TP") (pintype "input"))
    )
    (net (code "101") (name "SWO") (class "Default")
      (node (ref "SCL") (pin "P$AD22") (pinfunction "P1.00_P$AD22") (pintype "bidirectional"))
      (node (ref "TP_SWO") (pin "TP") (pinfunction "TP_TP") (pintype "input"))
    )
    (net (code "102") (name "VBAT") (class "Default")
      (node (ref "C27") (pin "2") (pinfunction "2_2") (pintype "passive"))
      (node (ref "TP_VBAT") (pin "TP") (pinfunction "TP_TP") (pintype "input"))
      (node (ref "U3") (pin "2") (pinfunction "CELL_2") (pintype "power_in"))
      (node (ref "U3") (pin "3") (pinfunction "VDD_3") (pintype "power_in"))
    )
    (net (code "103") (name "VBAT{slash}2.5C") (class "Default")
      (node (ref "C37") (pin "2") (pinfunction "2_2") (pintype "passive"))
      (node (ref "IC1") (pin "C2") (pinfunction "BAT_C2") (pintype "bidirectional"))
    )
    (net (code "104") (name "VBUS") (class "Default")
      (node (ref "C21") (pin "1") (pinfunction "1_1") (pintype "passive"))
      (node (ref "C38") (pin "2") (pinfunction "2_2") (pintype "passive"))
      (node (ref "C42") (pin "1") (pinfunction "1_1") (pintype "passive"))
      (node (ref "C43") (pin "1") (pinfunction "1_1") (pintype "passive"))
      (node (ref "D3") (pin "5") (pinfunction "VBUS_5") (pintype "bidirectional"))
      (node (ref "IC1") (pin "A2") (pinfunction "IN_A2") (pintype "bidirectional"))
      (node (ref "J4") (pin "A4_B9") (pinfunction "VBUS_A4_B9") (pintype "power_in"))
      (node (ref "J4") (pin "A9_B4") (pinfunction "VBUS_A9_B4") (pintype "power_in"))
      (node (ref "SCL") (pin "P$AD2") (pinfunction "VBUS_P$AD2") (pintype "power_in"))
    )
    (net (code "105") (name "VREG") (class "Default")
      (node (ref "C23") (pin "2") (pinfunction "2_2") (pintype "passive"))
      (node (ref "C24") (pin "2") (pinfunction "2_2") (pintype "passive"))
      (node (ref "C39") (pin "1") (pinfunction "1_1") (pintype "passive"))
      (node (ref "IC1") (pin "B2") (pinfunction "SYS_B2") (pintype "bidirectional"))
      (node (ref "IC9") (pin "A1") (pinfunction "EN_A1") (pintype "bidirectional"))
      (node (ref "IC9") (pin "A2") (pinfunction "VIN_1_A2") (pintype "bidirectional"))
      (node (ref "IC9") (pin "A3") (pinfunction "VIN_2_A3") (pintype "bidirectional"))
      (node (ref "TP_VREG") (pin "TP") (pinfunction "TP_TP") (pintype "input"))
    )
    (net (code "106") (name "unconnected-(ANT1-NC-Pad2)") (class "Default")
      (node (ref "ANT1") (pin "2") (pinfunction "NC_2") (pintype "no_connect"))
    )
    (net (code "107") (name "unconnected-(IC3-ASCL-Pad11)") (class "Default")
      (node (ref "IC3") (pin "11") (pinfunction "ASCL_11") (pintype "bidirectional"))
    )
    (net (code "108") (name "unconnected-(IC3-ASDA-Pad4)") (class "Default")
      (node (ref "IC3") (pin "4") (pinfunction "ASDA_4") (pintype "bidirectional"))
    )
    (net (code "109") (name "unconnected-(J1-Pad1)") (class "Default")
      (node (ref "J1") (pin "1") (pinfunction "1_1") (pintype "bidirectional"))
    )
    (net (code "110") (name "unconnected-(J1-Pad6)") (class "Default")
      (node (ref "J1") (pin "6") (pinfunction "6_6") (pintype "bidirectional"))
    )
    (net (code "111") (name "unconnected-(J1-Pad7)") (class "Default")
      (node (ref "J1") (pin "7") (pinfunction "7_7") (pintype "bidirectional"))
    )
    (net (code "112") (name "unconnected-(J4-SBU1-PadA8)") (class "Default")
      (node (ref "J4") (pin "A8") (pinfunction "SBU1_A8") (pintype "bidirectional"))
    )
    (net (code "113") (name "unconnected-(J4-SBU2-PadB8)") (class "Default")
      (node (ref "J4") (pin "B8") (pinfunction "SBU2_B8") (pintype "bidirectional"))
    )
    (net (code "114") (name "unconnected-(SCL-DCCH-PadP$AB2)") (class "Default")
      (node (ref "SCL") (pin "P$AB2") (pinfunction "DCCH_P$AB2") (pintype "bidirectional"))
    )
  )
)
